# romboard.net
KiCad netlist of a schematic drawn in EAGLE
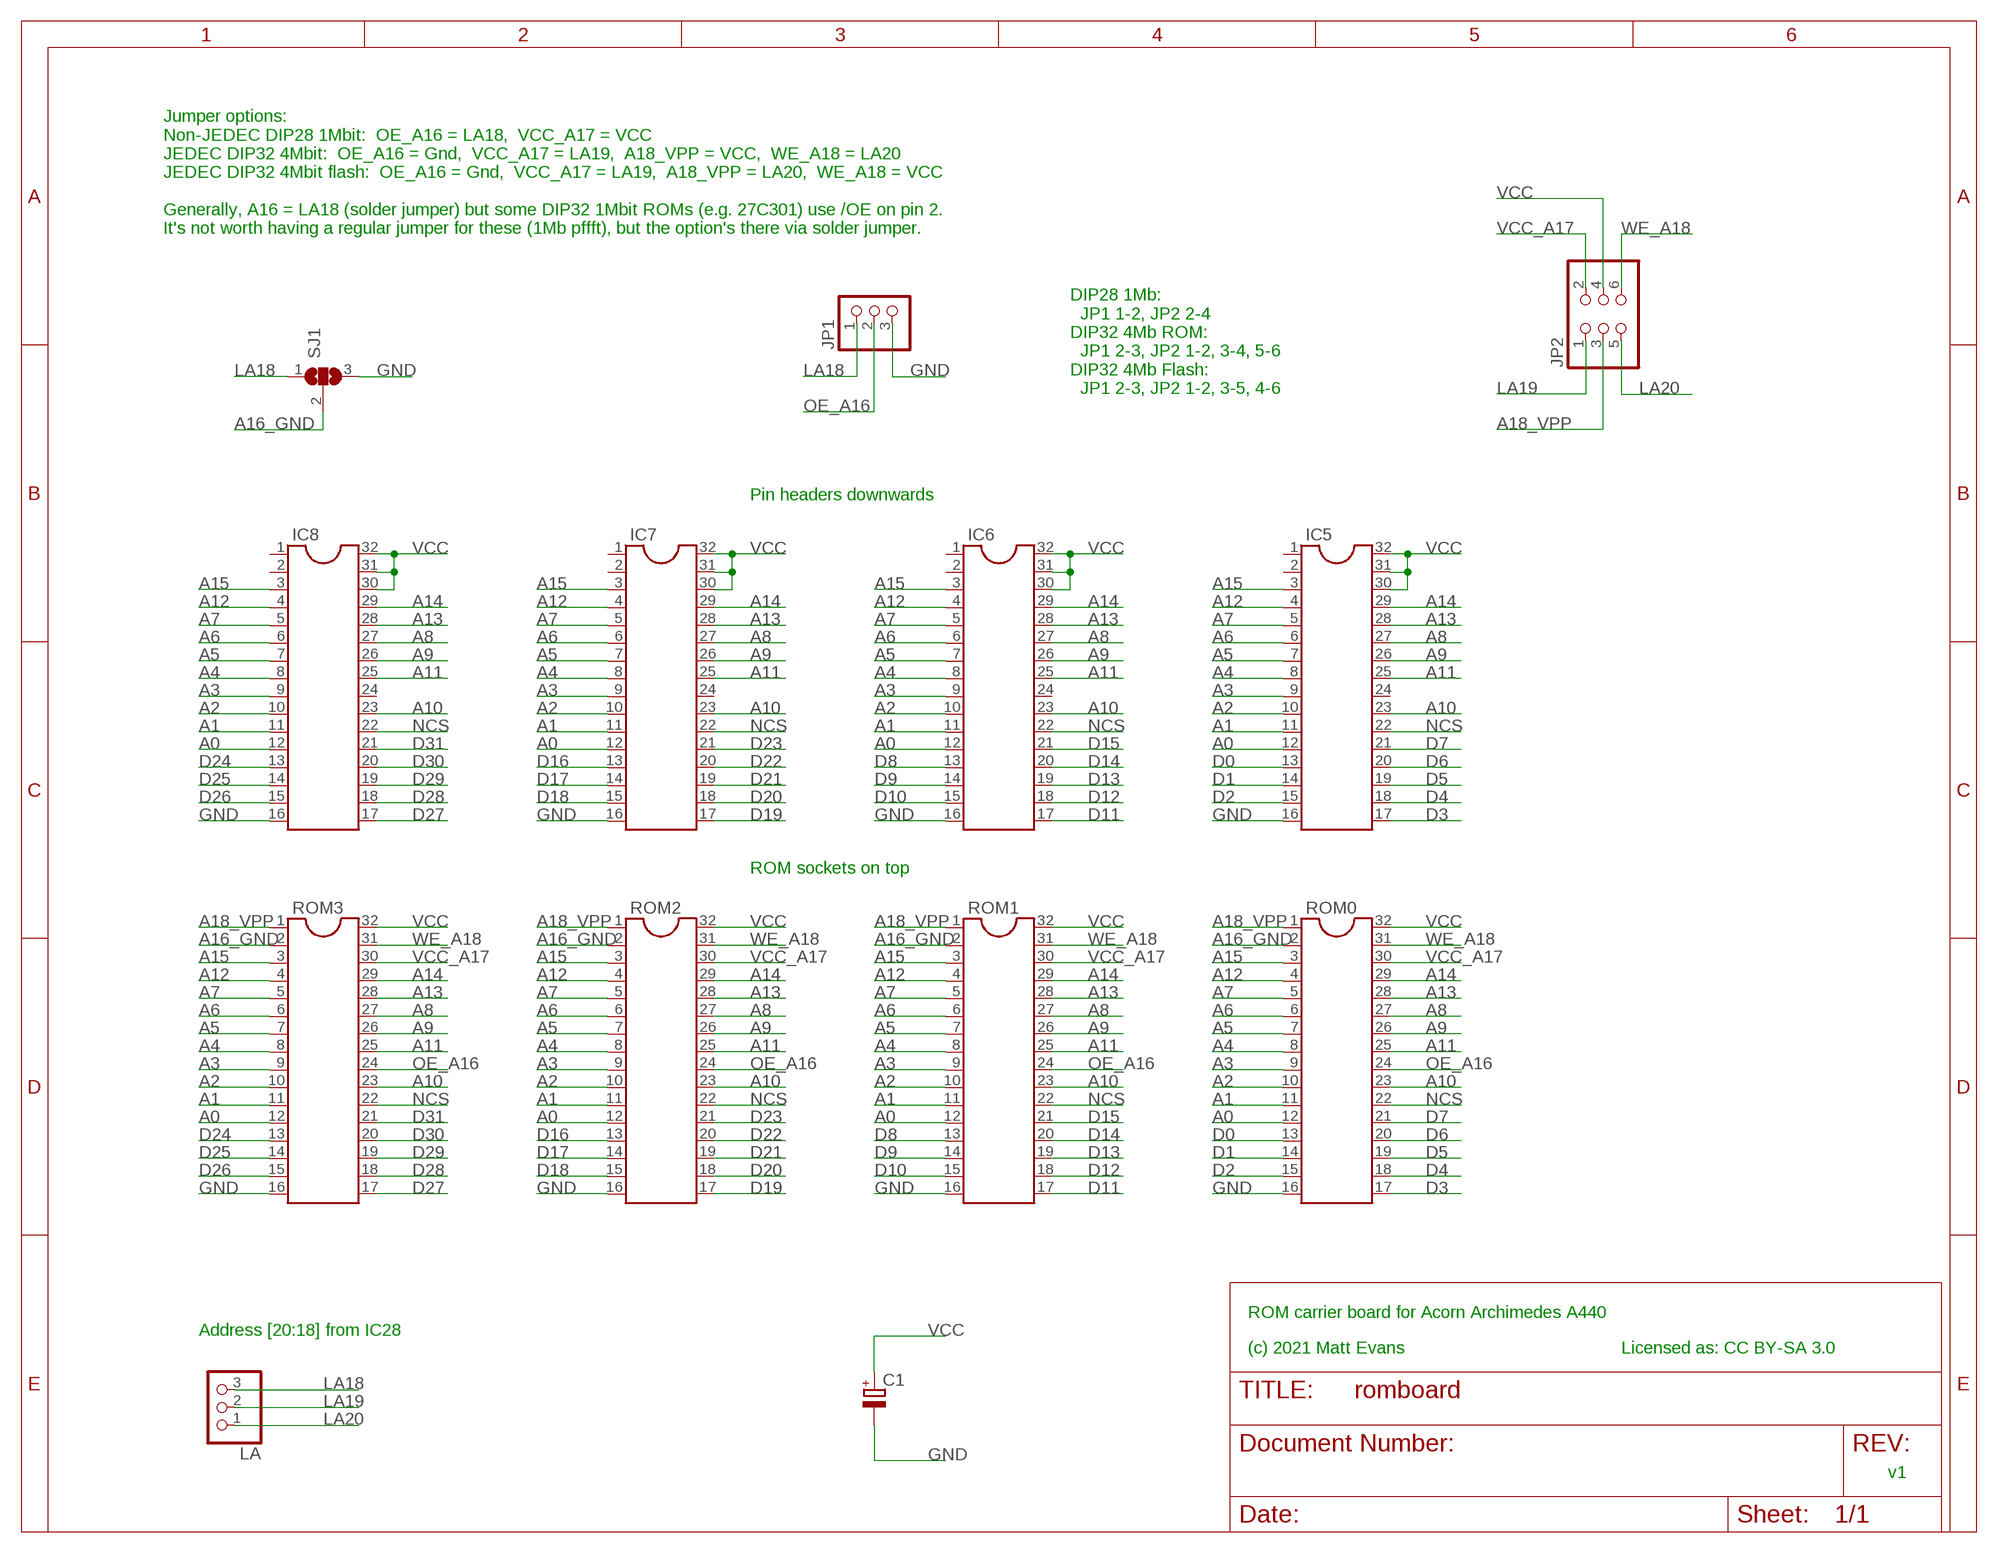
[diagram p0: schematic, sheet 1]

(export (version "E")
  (design (tool "Eeschema 10.0.6"))
  (components
    (comp (ref "C1")
      (value "CPOL-EU085CS-1AR")
      (footprint "eagle-import:085CS_1AR")
      (libsource (lib "eagle-import") (part "CPOL-EU085CS-1AR"))
    )
    (comp (ref "IC5")
      (value "DIL32")
      (footprint "eagle-import:DIL32")
      (libsource (lib "eagle-import") (part "DIL32"))
    )
    (comp (ref "IC6")
      (value "DIL32")
      (footprint "eagle-import:DIL32")
      (libsource (lib "eagle-import") (part "DIL32"))
    )
    (comp (ref "IC7")
      (value "DIL32")
      (footprint "eagle-import:DIL32")
      (libsource (lib "eagle-import") (part "DIL32"))
    )
    (comp (ref "IC8")
      (value "DIL32")
      (footprint "eagle-import:DIL32")
      (libsource (lib "eagle-import") (part "DIL32"))
    )
    (comp (ref "JP1")
      (value "PINHD-1X3")
      (footprint "eagle-import:1X03")
      (libsource (lib "eagle-import") (part "PINHD-1X3"))
    )
    (comp (ref "JP2")
      (value "PINHD-2X3")
      (footprint "eagle-import:2X03")
      (libsource (lib "eagle-import") (part "PINHD-2X3"))
    )
    (comp (ref "LA")
      (value "PINHD-1X3/90")
      (footprint "eagle-import:1X03_90")
      (libsource (lib "eagle-import") (part "pinhead_PINHD-1X3/90"))
    )
    (comp (ref "ROM0")
      (value "DIL32")
      (footprint "eagle-import:DIL32")
      (libsource (lib "eagle-import") (part "DIL32"))
    )
    (comp (ref "ROM1")
      (value "DIL32")
      (footprint "eagle-import:DIL32")
      (libsource (lib "eagle-import") (part "DIL32"))
    )
    (comp (ref "ROM2")
      (value "DIL32")
      (footprint "eagle-import:DIL32")
      (libsource (lib "eagle-import") (part "DIL32"))
    )
    (comp (ref "ROM3")
      (value "DIL32")
      (footprint "eagle-import:DIL32")
      (libsource (lib "eagle-import") (part "DIL32"))
    )
    (comp (ref "SJ1")
      (value "SJ2W")
      (footprint "eagle-import:SJ_2")
      (libsource (lib "eagle-import") (part "SJ2W"))
    )
  )
  (nets
    (net (code "1") (name "/A0") (class "Default")
      (node (ref "IC5") (pin "12") (pinfunction "12_12") (pintype "passive"))
      (node (ref "IC6") (pin "12") (pinfunction "12_12") (pintype "passive"))
      (node (ref "IC7") (pin "12") (pinfunction "12_12") (pintype "passive"))
      (node (ref "IC8") (pin "12") (pinfunction "12_12") (pintype "passive"))
      (node (ref "ROM0") (pin "12") (pinfunction "12_12") (pintype "passive"))
      (node (ref "ROM1") (pin "12") (pinfunction "12_12") (pintype "passive"))
      (node (ref "ROM2") (pin "12") (pinfunction "12_12") (pintype "passive"))
      (node (ref "ROM3") (pin "12") (pinfunction "12_12") (pintype "passive"))
    )
    (net (code "2") (name "/A1") (class "Default")
      (node (ref "IC5") (pin "11") (pinfunction "11_11") (pintype "passive"))
      (node (ref "IC6") (pin "11") (pinfunction "11_11") (pintype "passive"))
      (node (ref "IC7") (pin "11") (pinfunction "11_11") (pintype "passive"))
      (node (ref "IC8") (pin "11") (pinfunction "11_11") (pintype "passive"))
      (node (ref "ROM0") (pin "11") (pinfunction "11_11") (pintype "passive"))
      (node (ref "ROM1") (pin "11") (pinfunction "11_11") (pintype "passive"))
      (node (ref "ROM2") (pin "11") (pinfunction "11_11") (pintype "passive"))
      (node (ref "ROM3") (pin "11") (pinfunction "11_11") (pintype "passive"))
    )
    (net (code "3") (name "/A2") (class "Default")
      (node (ref "IC5") (pin "10") (pinfunction "10_10") (pintype "passive"))
      (node (ref "IC6") (pin "10") (pinfunction "10_10") (pintype "passive"))
      (node (ref "IC7") (pin "10") (pinfunction "10_10") (pintype "passive"))
      (node (ref "IC8") (pin "10") (pinfunction "10_10") (pintype "passive"))
      (node (ref "ROM0") (pin "10") (pinfunction "10_10") (pintype "passive"))
      (node (ref "ROM1") (pin "10") (pinfunction "10_10") (pintype "passive"))
      (node (ref "ROM2") (pin "10") (pinfunction "10_10") (pintype "passive"))
      (node (ref "ROM3") (pin "10") (pinfunction "10_10") (pintype "passive"))
    )
    (net (code "4") (name "/A3") (class "Default")
      (node (ref "IC5") (pin "9") (pinfunction "9_9") (pintype "passive"))
      (node (ref "IC6") (pin "9") (pinfunction "9_9") (pintype "passive"))
      (node (ref "IC7") (pin "9") (pinfunction "9_9") (pintype "passive"))
      (node (ref "IC8") (pin "9") (pinfunction "9_9") (pintype "passive"))
      (node (ref "ROM0") (pin "9") (pinfunction "9_9") (pintype "passive"))
      (node (ref "ROM1") (pin "9") (pinfunction "9_9") (pintype "passive"))
      (node (ref "ROM2") (pin "9") (pinfunction "9_9") (pintype "passive"))
      (node (ref "ROM3") (pin "9") (pinfunction "9_9") (pintype "passive"))
    )
    (net (code "5") (name "/A4") (class "Default")
      (node (ref "IC5") (pin "8") (pinfunction "8_8") (pintype "passive"))
      (node (ref "IC6") (pin "8") (pinfunction "8_8") (pintype "passive"))
      (node (ref "IC7") (pin "8") (pinfunction "8_8") (pintype "passive"))
      (node (ref "IC8") (pin "8") (pinfunction "8_8") (pintype "passive"))
      (node (ref "ROM0") (pin "8") (pinfunction "8_8") (pintype "passive"))
      (node (ref "ROM1") (pin "8") (pinfunction "8_8") (pintype "passive"))
      (node (ref "ROM2") (pin "8") (pinfunction "8_8") (pintype "passive"))
      (node (ref "ROM3") (pin "8") (pinfunction "8_8") (pintype "passive"))
    )
    (net (code "6") (name "/A5") (class "Default")
      (node (ref "IC5") (pin "7") (pinfunction "7_7") (pintype "passive"))
      (node (ref "IC6") (pin "7") (pinfunction "7_7") (pintype "passive"))
      (node (ref "IC7") (pin "7") (pinfunction "7_7") (pintype "passive"))
      (node (ref "IC8") (pin "7") (pinfunction "7_7") (pintype "passive"))
      (node (ref "ROM0") (pin "7") (pinfunction "7_7") (pintype "passive"))
      (node (ref "ROM1") (pin "7") (pinfunction "7_7") (pintype "passive"))
      (node (ref "ROM2") (pin "7") (pinfunction "7_7") (pintype "passive"))
      (node (ref "ROM3") (pin "7") (pinfunction "7_7") (pintype "passive"))
    )
    (net (code "7") (name "/A6") (class "Default")
      (node (ref "IC5") (pin "6") (pinfunction "6_6") (pintype "passive"))
      (node (ref "IC6") (pin "6") (pinfunction "6_6") (pintype "passive"))
      (node (ref "IC7") (pin "6") (pinfunction "6_6") (pintype "passive"))
      (node (ref "IC8") (pin "6") (pinfunction "6_6") (pintype "passive"))
      (node (ref "ROM0") (pin "6") (pinfunction "6_6") (pintype "passive"))
      (node (ref "ROM1") (pin "6") (pinfunction "6_6") (pintype "passive"))
      (node (ref "ROM2") (pin "6") (pinfunction "6_6") (pintype "passive"))
      (node (ref "ROM3") (pin "6") (pinfunction "6_6") (pintype "passive"))
    )
    (net (code "8") (name "/A7") (class "Default")
      (node (ref "IC5") (pin "5") (pinfunction "5_5") (pintype "passive"))
      (node (ref "IC6") (pin "5") (pinfunction "5_5") (pintype "passive"))
      (node (ref "IC7") (pin "5") (pinfunction "5_5") (pintype "passive"))
      (node (ref "IC8") (pin "5") (pinfunction "5_5") (pintype "passive"))
      (node (ref "ROM0") (pin "5") (pinfunction "5_5") (pintype "passive"))
      (node (ref "ROM1") (pin "5") (pinfunction "5_5") (pintype "passive"))
      (node (ref "ROM2") (pin "5") (pinfunction "5_5") (pintype "passive"))
      (node (ref "ROM3") (pin "5") (pinfunction "5_5") (pintype "passive"))
    )
    (net (code "9") (name "/A8") (class "Default")
      (node (ref "IC5") (pin "27") (pinfunction "27_27") (pintype "passive"))
      (node (ref "IC6") (pin "27") (pinfunction "27_27") (pintype "passive"))
      (node (ref "IC7") (pin "27") (pinfunction "27_27") (pintype "passive"))
      (node (ref "IC8") (pin "27") (pinfunction "27_27") (pintype "passive"))
      (node (ref "ROM0") (pin "27") (pinfunction "27_27") (pintype "passive"))
      (node (ref "ROM1") (pin "27") (pinfunction "27_27") (pintype "passive"))
      (node (ref "ROM2") (pin "27") (pinfunction "27_27") (pintype "passive"))
      (node (ref "ROM3") (pin "27") (pinfunction "27_27") (pintype "passive"))
    )
    (net (code "10") (name "/A9") (class "Default")
      (node (ref "IC5") (pin "26") (pinfunction "26_26") (pintype "passive"))
      (node (ref "IC6") (pin "26") (pinfunction "26_26") (pintype "passive"))
      (node (ref "IC7") (pin "26") (pinfunction "26_26") (pintype "passive"))
      (node (ref "IC8") (pin "26") (pinfunction "26_26") (pintype "passive"))
      (node (ref "ROM0") (pin "26") (pinfunction "26_26") (pintype "passive"))
      (node (ref "ROM1") (pin "26") (pinfunction "26_26") (pintype "passive"))
      (node (ref "ROM2") (pin "26") (pinfunction "26_26") (pintype "passive"))
      (node (ref "ROM3") (pin "26") (pinfunction "26_26") (pintype "passive"))
    )
    (net (code "11") (name "/A10") (class "Default")
      (node (ref "IC5") (pin "23") (pinfunction "23_23") (pintype "passive"))
      (node (ref "IC6") (pin "23") (pinfunction "23_23") (pintype "passive"))
      (node (ref "IC7") (pin "23") (pinfunction "23_23") (pintype "passive"))
      (node (ref "IC8") (pin "23") (pinfunction "23_23") (pintype "passive"))
      (node (ref "ROM0") (pin "23") (pinfunction "23_23") (pintype "passive"))
      (node (ref "ROM1") (pin "23") (pinfunction "23_23") (pintype "passive"))
      (node (ref "ROM2") (pin "23") (pinfunction "23_23") (pintype "passive"))
      (node (ref "ROM3") (pin "23") (pinfunction "23_23") (pintype "passive"))
    )
    (net (code "12") (name "/A11") (class "Default")
      (node (ref "IC5") (pin "25") (pinfunction "25_25") (pintype "passive"))
      (node (ref "IC6") (pin "25") (pinfunction "25_25") (pintype "passive"))
      (node (ref "IC7") (pin "25") (pinfunction "25_25") (pintype "passive"))
      (node (ref "IC8") (pin "25") (pinfunction "25_25") (pintype "passive"))
      (node (ref "ROM0") (pin "25") (pinfunction "25_25") (pintype "passive"))
      (node (ref "ROM1") (pin "25") (pinfunction "25_25") (pintype "passive"))
      (node (ref "ROM2") (pin "25") (pinfunction "25_25") (pintype "passive"))
      (node (ref "ROM3") (pin "25") (pinfunction "25_25") (pintype "passive"))
    )
    (net (code "13") (name "/A12") (class "Default")
      (node (ref "IC5") (pin "4") (pinfunction "4_4") (pintype "passive"))
      (node (ref "IC6") (pin "4") (pinfunction "4_4") (pintype "passive"))
      (node (ref "IC7") (pin "4") (pinfunction "4_4") (pintype "passive"))
      (node (ref "IC8") (pin "4") (pinfunction "4_4") (pintype "passive"))
      (node (ref "ROM0") (pin "4") (pinfunction "4_4") (pintype "passive"))
      (node (ref "ROM1") (pin "4") (pinfunction "4_4") (pintype "passive"))
      (node (ref "ROM2") (pin "4") (pinfunction "4_4") (pintype "passive"))
      (node (ref "ROM3") (pin "4") (pinfunction "4_4") (pintype "passive"))
    )
    (net (code "14") (name "/A13") (class "Default")
      (node (ref "IC5") (pin "28") (pinfunction "28_28") (pintype "passive"))
      (node (ref "IC6") (pin "28") (pinfunction "28_28") (pintype "passive"))
      (node (ref "IC7") (pin "28") (pinfunction "28_28") (pintype "passive"))
      (node (ref "IC8") (pin "28") (pinfunction "28_28") (pintype "passive"))
      (node (ref "ROM0") (pin "28") (pinfunction "28_28") (pintype "passive"))
      (node (ref "ROM1") (pin "28") (pinfunction "28_28") (pintype "passive"))
      (node (ref "ROM2") (pin "28") (pinfunction "28_28") (pintype "passive"))
      (node (ref "ROM3") (pin "28") (pinfunction "28_28") (pintype "passive"))
    )
    (net (code "15") (name "/A14") (class "Default")
      (node (ref "IC5") (pin "29") (pinfunction "29_29") (pintype "passive"))
      (node (ref "IC6") (pin "29") (pinfunction "29_29") (pintype "passive"))
      (node (ref "IC7") (pin "29") (pinfunction "29_29") (pintype "passive"))
      (node (ref "IC8") (pin "29") (pinfunction "29_29") (pintype "passive"))
      (node (ref "ROM0") (pin "29") (pinfunction "29_29") (pintype "passive"))
      (node (ref "ROM1") (pin "29") (pinfunction "29_29") (pintype "passive"))
      (node (ref "ROM2") (pin "29") (pinfunction "29_29") (pintype "passive"))
      (node (ref "ROM3") (pin "29") (pinfunction "29_29") (pintype "passive"))
    )
    (net (code "16") (name "/A15") (class "Default")
      (node (ref "IC5") (pin "3") (pinfunction "3_3") (pintype "passive"))
      (node (ref "IC6") (pin "3") (pinfunction "3_3") (pintype "passive"))
      (node (ref "IC7") (pin "3") (pinfunction "3_3") (pintype "passive"))
      (node (ref "IC8") (pin "3") (pinfunction "3_3") (pintype "passive"))
      (node (ref "ROM0") (pin "3") (pinfunction "3_3") (pintype "passive"))
      (node (ref "ROM1") (pin "3") (pinfunction "3_3") (pintype "passive"))
      (node (ref "ROM2") (pin "3") (pinfunction "3_3") (pintype "passive"))
      (node (ref "ROM3") (pin "3") (pinfunction "3_3") (pintype "passive"))
    )
    (net (code "17") (name "/A16_GND") (class "Default")
      (node (ref "ROM0") (pin "2") (pinfunction "2_2") (pintype "passive"))
      (node (ref "ROM1") (pin "2") (pinfunction "2_2") (pintype "passive"))
      (node (ref "ROM2") (pin "2") (pinfunction "2_2") (pintype "passive"))
      (node (ref "ROM3") (pin "2") (pinfunction "2_2") (pintype "passive"))
      (node (ref "SJ1") (pin "2") (pinfunction "2_2") (pintype "passive"))
    )
    (net (code "18") (name "/A18_VPP") (class "Default")
      (node (ref "JP2") (pin "3") (pinfunction "3_3") (pintype "passive"))
      (node (ref "ROM0") (pin "1") (pinfunction "1_1") (pintype "passive"))
      (node (ref "ROM1") (pin "1") (pinfunction "1_1") (pintype "passive"))
      (node (ref "ROM2") (pin "1") (pinfunction "1_1") (pintype "passive"))
      (node (ref "ROM3") (pin "1") (pinfunction "1_1") (pintype "passive"))
    )
    (net (code "19") (name "/D0") (class "Default")
      (node (ref "IC5") (pin "13") (pinfunction "13_13") (pintype "passive"))
      (node (ref "ROM0") (pin "13") (pinfunction "13_13") (pintype "passive"))
    )
    (net (code "20") (name "/D1") (class "Default")
      (node (ref "IC5") (pin "14") (pinfunction "14_14") (pintype "passive"))
      (node (ref "ROM0") (pin "14") (pinfunction "14_14") (pintype "passive"))
    )
    (net (code "21") (name "/D2") (class "Default")
      (node (ref "IC5") (pin "15") (pinfunction "15_15") (pintype "passive"))
      (node (ref "ROM0") (pin "15") (pinfunction "15_15") (pintype "passive"))
    )
    (net (code "22") (name "/D3") (class "Default")
      (node (ref "IC5") (pin "17") (pinfunction "17_17") (pintype "passive"))
      (node (ref "ROM0") (pin "17") (pinfunction "17_17") (pintype "passive"))
    )
    (net (code "23") (name "/D4") (class "Default")
      (node (ref "IC5") (pin "18") (pinfunction "18_18") (pintype "passive"))
      (node (ref "ROM0") (pin "18") (pinfunction "18_18") (pintype "passive"))
    )
    (net (code "24") (name "/D5") (class "Default")
      (node (ref "IC5") (pin "19") (pinfunction "19_19") (pintype "passive"))
      (node (ref "ROM0") (pin "19") (pinfunction "19_19") (pintype "passive"))
    )
    (net (code "25") (name "/D6") (class "Default")
      (node (ref "IC5") (pin "20") (pinfunction "20_20") (pintype "passive"))
      (node (ref "ROM0") (pin "20") (pinfunction "20_20") (pintype "passive"))
    )
    (net (code "26") (name "/D7") (class "Default")
      (node (ref "IC5") (pin "21") (pinfunction "21_21") (pintype "passive"))
      (node (ref "ROM0") (pin "21") (pinfunction "21_21") (pintype "passive"))
    )
    (net (code "27") (name "/D8") (class "Default")
      (node (ref "IC6") (pin "13") (pinfunction "13_13") (pintype "passive"))
      (node (ref "ROM1") (pin "13") (pinfunction "13_13") (pintype "passive"))
    )
    (net (code "28") (name "/D9") (class "Default")
      (node (ref "IC6") (pin "14") (pinfunction "14_14") (pintype "passive"))
      (node (ref "ROM1") (pin "14") (pinfunction "14_14") (pintype "passive"))
    )
    (net (code "29") (name "/D10") (class "Default")
      (node (ref "IC6") (pin "15") (pinfunction "15_15") (pintype "passive"))
      (node (ref "ROM1") (pin "15") (pinfunction "15_15") (pintype "passive"))
    )
    (net (code "30") (name "/D11") (class "Default")
      (node (ref "IC6") (pin "17") (pinfunction "17_17") (pintype "passive"))
      (node (ref "ROM1") (pin "17") (pinfunction "17_17") (pintype "passive"))
    )
    (net (code "31") (name "/D12") (class "Default")
      (node (ref "IC6") (pin "18") (pinfunction "18_18") (pintype "passive"))
      (node (ref "ROM1") (pin "18") (pinfunction "18_18") (pintype "passive"))
    )
    (net (code "32") (name "/D13") (class "Default")
      (node (ref "IC6") (pin "19") (pinfunction "19_19") (pintype "passive"))
      (node (ref "ROM1") (pin "19") (pinfunction "19_19") (pintype "passive"))
    )
    (net (code "33") (name "/D14") (class "Default")
      (node (ref "IC6") (pin "20") (pinfunction "20_20") (pintype "passive"))
      (node (ref "ROM1") (pin "20") (pinfunction "20_20") (pintype "passive"))
    )
    (net (code "34") (name "/D15") (class "Default")
      (node (ref "IC6") (pin "21") (pinfunction "21_21") (pintype "passive"))
      (node (ref "ROM1") (pin "21") (pinfunction "21_21") (pintype "passive"))
    )
    (net (code "35") (name "/D16") (class "Default")
      (node (ref "IC7") (pin "13") (pinfunction "13_13") (pintype "passive"))
      (node (ref "ROM2") (pin "13") (pinfunction "13_13") (pintype "passive"))
    )
    (net (code "36") (name "/D17") (class "Default")
      (node (ref "IC7") (pin "14") (pinfunction "14_14") (pintype "passive"))
      (node (ref "ROM2") (pin "14") (pinfunction "14_14") (pintype "passive"))
    )
    (net (code "37") (name "/D18") (class "Default")
      (node (ref "IC7") (pin "15") (pinfunction "15_15") (pintype "passive"))
      (node (ref "ROM2") (pin "15") (pinfunction "15_15") (pintype "passive"))
    )
    (net (code "38") (name "/D19") (class "Default")
      (node (ref "IC7") (pin "17") (pinfunction "17_17") (pintype "passive"))
      (node (ref "ROM2") (pin "17") (pinfunction "17_17") (pintype "passive"))
    )
    (net (code "39") (name "/D20") (class "Default")
      (node (ref "IC7") (pin "18") (pinfunction "18_18") (pintype "passive"))
      (node (ref "ROM2") (pin "18") (pinfunction "18_18") (pintype "passive"))
    )
    (net (code "40") (name "/D21") (class "Default")
      (node (ref "IC7") (pin "19") (pinfunction "19_19") (pintype "passive"))
      (node (ref "ROM2") (pin "19") (pinfunction "19_19") (pintype "passive"))
    )
    (net (code "41") (name "/D22") (class "Default")
      (node (ref "IC7") (pin "20") (pinfunction "20_20") (pintype "passive"))
      (node (ref "ROM2") (pin "20") (pinfunction "20_20") (pintype "passive"))
    )
    (net (code "42") (name "/D23") (class "Default")
      (node (ref "IC7") (pin "21") (pinfunction "21_21") (pintype "passive"))
      (node (ref "ROM2") (pin "21") (pinfunction "21_21") (pintype "passive"))
    )
    (net (code "43") (name "/D24") (class "Default")
      (node (ref "IC8") (pin "13") (pinfunction "13_13") (pintype "passive"))
      (node (ref "ROM3") (pin "13") (pinfunction "13_13") (pintype "passive"))
    )
    (net (code "44") (name "/D25") (class "Default")
      (node (ref "IC8") (pin "14") (pinfunction "14_14") (pintype "passive"))
      (node (ref "ROM3") (pin "14") (pinfunction "14_14") (pintype "passive"))
    )
    (net (code "45") (name "/D26") (class "Default")
      (node (ref "IC8") (pin "15") (pinfunction "15_15") (pintype "passive"))
      (node (ref "ROM3") (pin "15") (pinfunction "15_15") (pintype "passive"))
    )
    (net (code "46") (name "/D27") (class "Default")
      (node (ref "IC8") (pin "17") (pinfunction "17_17") (pintype "passive"))
      (node (ref "ROM3") (pin "17") (pinfunction "17_17") (pintype "passive"))
    )
    (net (code "47") (name "/D28") (class "Default")
      (node (ref "IC8") (pin "18") (pinfunction "18_18") (pintype "passive"))
      (node (ref "ROM3") (pin "18") (pinfunction "18_18") (pintype "passive"))
    )
    (net (code "48") (name "/D29") (class "Default")
      (node (ref "IC8") (pin "19") (pinfunction "19_19") (pintype "passive"))
      (node (ref "ROM3") (pin "19") (pinfunction "19_19") (pintype "passive"))
    )
    (net (code "49") (name "/D30") (class "Default")
      (node (ref "IC8") (pin "20") (pinfunction "20_20") (pintype "passive"))
      (node (ref "ROM3") (pin "20") (pinfunction "20_20") (pintype "passive"))
    )
    (net (code "50") (name "/D31") (class "Default")
      (node (ref "IC8") (pin "21") (pinfunction "21_21") (pintype "passive"))
      (node (ref "ROM3") (pin "21") (pinfunction "21_21") (pintype "passive"))
    )
    (net (code "51") (name "/GND") (class "Default")
      (node (ref "C1") (pin "-") (pinfunction "-_-") (pintype "passive"))
      (node (ref "IC5") (pin "16") (pinfunction "16_16") (pintype "passive"))
      (node (ref "IC6") (pin "16") (pinfunction "16_16") (pintype "passive"))
      (node (ref "IC7") (pin "16") (pinfunction "16_16") (pintype "passive"))
      (node (ref "IC8") (pin "16") (pinfunction "16_16") (pintype "passive"))
      (node (ref "JP1") (pin "3") (pinfunction "3_3") (pintype "passive"))
      (node (ref "ROM0") (pin "16") (pinfunction "16_16") (pintype "passive"))
      (node (ref "ROM1") (pin "16") (pinfunction "16_16") (pintype "passive"))
      (node (ref "ROM2") (pin "16") (pinfunction "16_16") (pintype "passive"))
      (node (ref "ROM3") (pin "16") (pinfunction "16_16") (pintype "passive"))
      (node (ref "SJ1") (pin "3") (pinfunction "3_3") (pintype "passive"))
    )
    (net (code "52") (name "/LA18") (class "Default")
      (node (ref "JP1") (pin "1") (pinfunction "1_1") (pintype "passive"))
      (node (ref "LA") (pin "3") (pinfunction "3_3") (pintype "passive"))
      (node (ref "SJ1") (pin "1") (pinfunction "1_1") (pintype "passive"))
    )
    (net (code "53") (name "/LA19") (class "Default")
      (node (ref "JP2") (pin "1") (pinfunction "1_1") (pintype "passive"))
      (node (ref "LA") (pin "2") (pinfunction "2_2") (pintype "passive"))
    )
    (net (code "54") (name "/LA20") (class "Default")
      (node (ref "JP2") (pin "5") (pinfunction "5_5") (pintype "passive"))
      (node (ref "LA") (pin "1") (pinfunction "1_1") (pintype "passive"))
    )
    (net (code "55") (name "/NCS") (class "Default")
      (node (ref "IC5") (pin "22") (pinfunction "22_22") (pintype "passive"))
      (node (ref "IC6") (pin "22") (pinfunction "22_22") (pintype "passive"))
      (node (ref "IC7") (pin "22") (pinfunction "22_22") (pintype "passive"))
      (node (ref "IC8") (pin "22") (pinfunction "22_22") (pintype "passive"))
      (node (ref "ROM0") (pin "22") (pinfunction "22_22") (pintype "passive"))
      (node (ref "ROM1") (pin "22") (pinfunction "22_22") (pintype "passive"))
      (node (ref "ROM2") (pin "22") (pinfunction "22_22") (pintype "passive"))
      (node (ref "ROM3") (pin "22") (pinfunction "22_22") (pintype "passive"))
    )
    (net (code "56") (name "/OE_A16") (class "Default")
      (node (ref "JP1") (pin "2") (pinfunction "2_2") (pintype "passive"))
      (node (ref "ROM0") (pin "24") (pinfunction "24_24") (pintype "passive"))
      (node (ref "ROM1") (pin "24") (pinfunction "24_24") (pintype "passive"))
      (node (ref "ROM2") (pin "24") (pinfunction "24_24") (pintype "passive"))
      (node (ref "ROM3") (pin "24") (pinfunction "24_24") (pintype "passive"))
    )
    (net (code "57") (name "/VCC") (class "Default")
      (node (ref "C1") (pin "+") (pinfunction "+_+") (pintype "passive"))
      (node (ref "IC5") (pin "30") (pinfunction "30_30") (pintype "passive"))
      (node (ref "IC5") (pin "31") (pinfunction "31_31") (pintype "passive"))
      (node (ref "IC5") (pin "32") (pinfunction "32_32") (pintype "passive"))
      (node (ref "IC6") (pin "30") (pinfunction "30_30") (pintype "passive"))
      (node (ref "IC6") (pin "31") (pinfunction "31_31") (pintype "passive"))
      (node (ref "IC6") (pin "32") (pinfunction "32_32") (pintype "passive"))
      (node (ref "IC7") (pin "30") (pinfunction "30_30") (pintype "passive"))
      (node (ref "IC7") (pin "31") (pinfunction "31_31") (pintype "passive"))
      (node (ref "IC7") (pin "32") (pinfunction "32_32") (pintype "passive"))
      (node (ref "IC8") (pin "30") (pinfunction "30_30") (pintype "passive"))
      (node (ref "IC8") (pin "31") (pinfunction "31_31") (pintype "passive"))
      (node (ref "IC8") (pin "32") (pinfunction "32_32") (pintype "passive"))
      (node (ref "JP2") (pin "4") (pinfunction "4_4") (pintype "passive"))
      (node (ref "ROM0") (pin "32") (pinfunction "32_32") (pintype "passive"))
      (node (ref "ROM1") (pin "32") (pinfunction "32_32") (pintype "passive"))
      (node (ref "ROM2") (pin "32") (pinfunction "32_32") (pintype "passive"))
      (node (ref "ROM3") (pin "32") (pinfunction "32_32") (pintype "passive"))
    )
    (net (code "58") (name "/VCC_A17") (class "Default")
      (node (ref "JP2") (pin "2") (pinfunction "2_2") (pintype "passive"))
      (node (ref "ROM0") (pin "30") (pinfunction "30_30") (pintype "passive"))
      (node (ref "ROM1") (pin "30") (pinfunction "30_30") (pintype "passive"))
      (node (ref "ROM2") (pin "30") (pinfunction "30_30") (pintype "passive"))
      (node (ref "ROM3") (pin "30") (pinfunction "30_30") (pintype "passive"))
    )
    (net (code "59") (name "/WE_A18") (class "Default")
      (node (ref "JP2") (pin "6") (pinfunction "6_6") (pintype "passive"))
      (node (ref "ROM0") (pin "31") (pinfunction "31_31") (pintype "passive"))
      (node (ref "ROM1") (pin "31") (pinfunction "31_31") (pintype "passive"))
      (node (ref "ROM2") (pin "31") (pinfunction "31_31") (pintype "passive"))
      (node (ref "ROM3") (pin "31") (pinfunction "31_31") (pintype "passive"))
    )
    (net (code "60") (name "unconnected-(IC5-Pad1)") (class "Default")
      (node (ref "IC5") (pin "1") (pinfunction "1_1") (pintype "passive"))
    )
    (net (code "61") (name "unconnected-(IC5-Pad2)") (class "Default")
      (node (ref "IC5") (pin "2") (pinfunction "2_2") (pintype "passive"))
    )
    (net (code "62") (name "unconnected-(IC5-Pad24)") (class "Default")
      (node (ref "IC5") (pin "24") (pinfunction "24_24") (pintype "passive"))
    )
    (net (code "63") (name "unconnected-(IC6-Pad1)") (class "Default")
      (node (ref "IC6") (pin "1") (pinfunction "1_1") (pintype "passive"))
    )
    (net (code "64") (name "unconnected-(IC6-Pad2)") (class "Default")
      (node (ref "IC6") (pin "2") (pinfunction "2_2") (pintype "passive"))
    )
    (net (code "65") (name "unconnected-(IC6-Pad24)") (class "Default")
      (node (ref "IC6") (pin "24") (pinfunction "24_24") (pintype "passive"))
    )
    (net (code "66") (name "unconnected-(IC7-Pad1)") (class "Default")
      (node (ref "IC7") (pin "1") (pinfunction "1_1") (pintype "passive"))
    )
    (net (code "67") (name "unconnected-(IC7-Pad2)") (class "Default")
      (node (ref "IC7") (pin "2") (pinfunction "2_2") (pintype "passive"))
    )
    (net (code "68") (name "unconnected-(IC7-Pad24)") (class "Default")
      (node (ref "IC7") (pin "24") (pinfunction "24_24") (pintype "passive"))
    )
    (net (code "69") (name "unconnected-(IC8-Pad1)") (class "Default")
      (node (ref "IC8") (pin "1") (pinfunction "1_1") (pintype "passive"))
    )
    (net (code "70") (name "unconnected-(IC8-Pad2)") (class "Default")
      (node (ref "IC8") (pin "2") (pinfunction "2_2") (pintype "passive"))
    )
    (net (code "71") (name "unconnected-(IC8-Pad24)") (class "Default")
      (node (ref "IC8") (pin "24") (pinfunction "24_24") (pintype "passive"))
    )
  )
)
